# UNIFC-F405.net
KiCad netlist of a schematic drawn in EasyEDA Pro
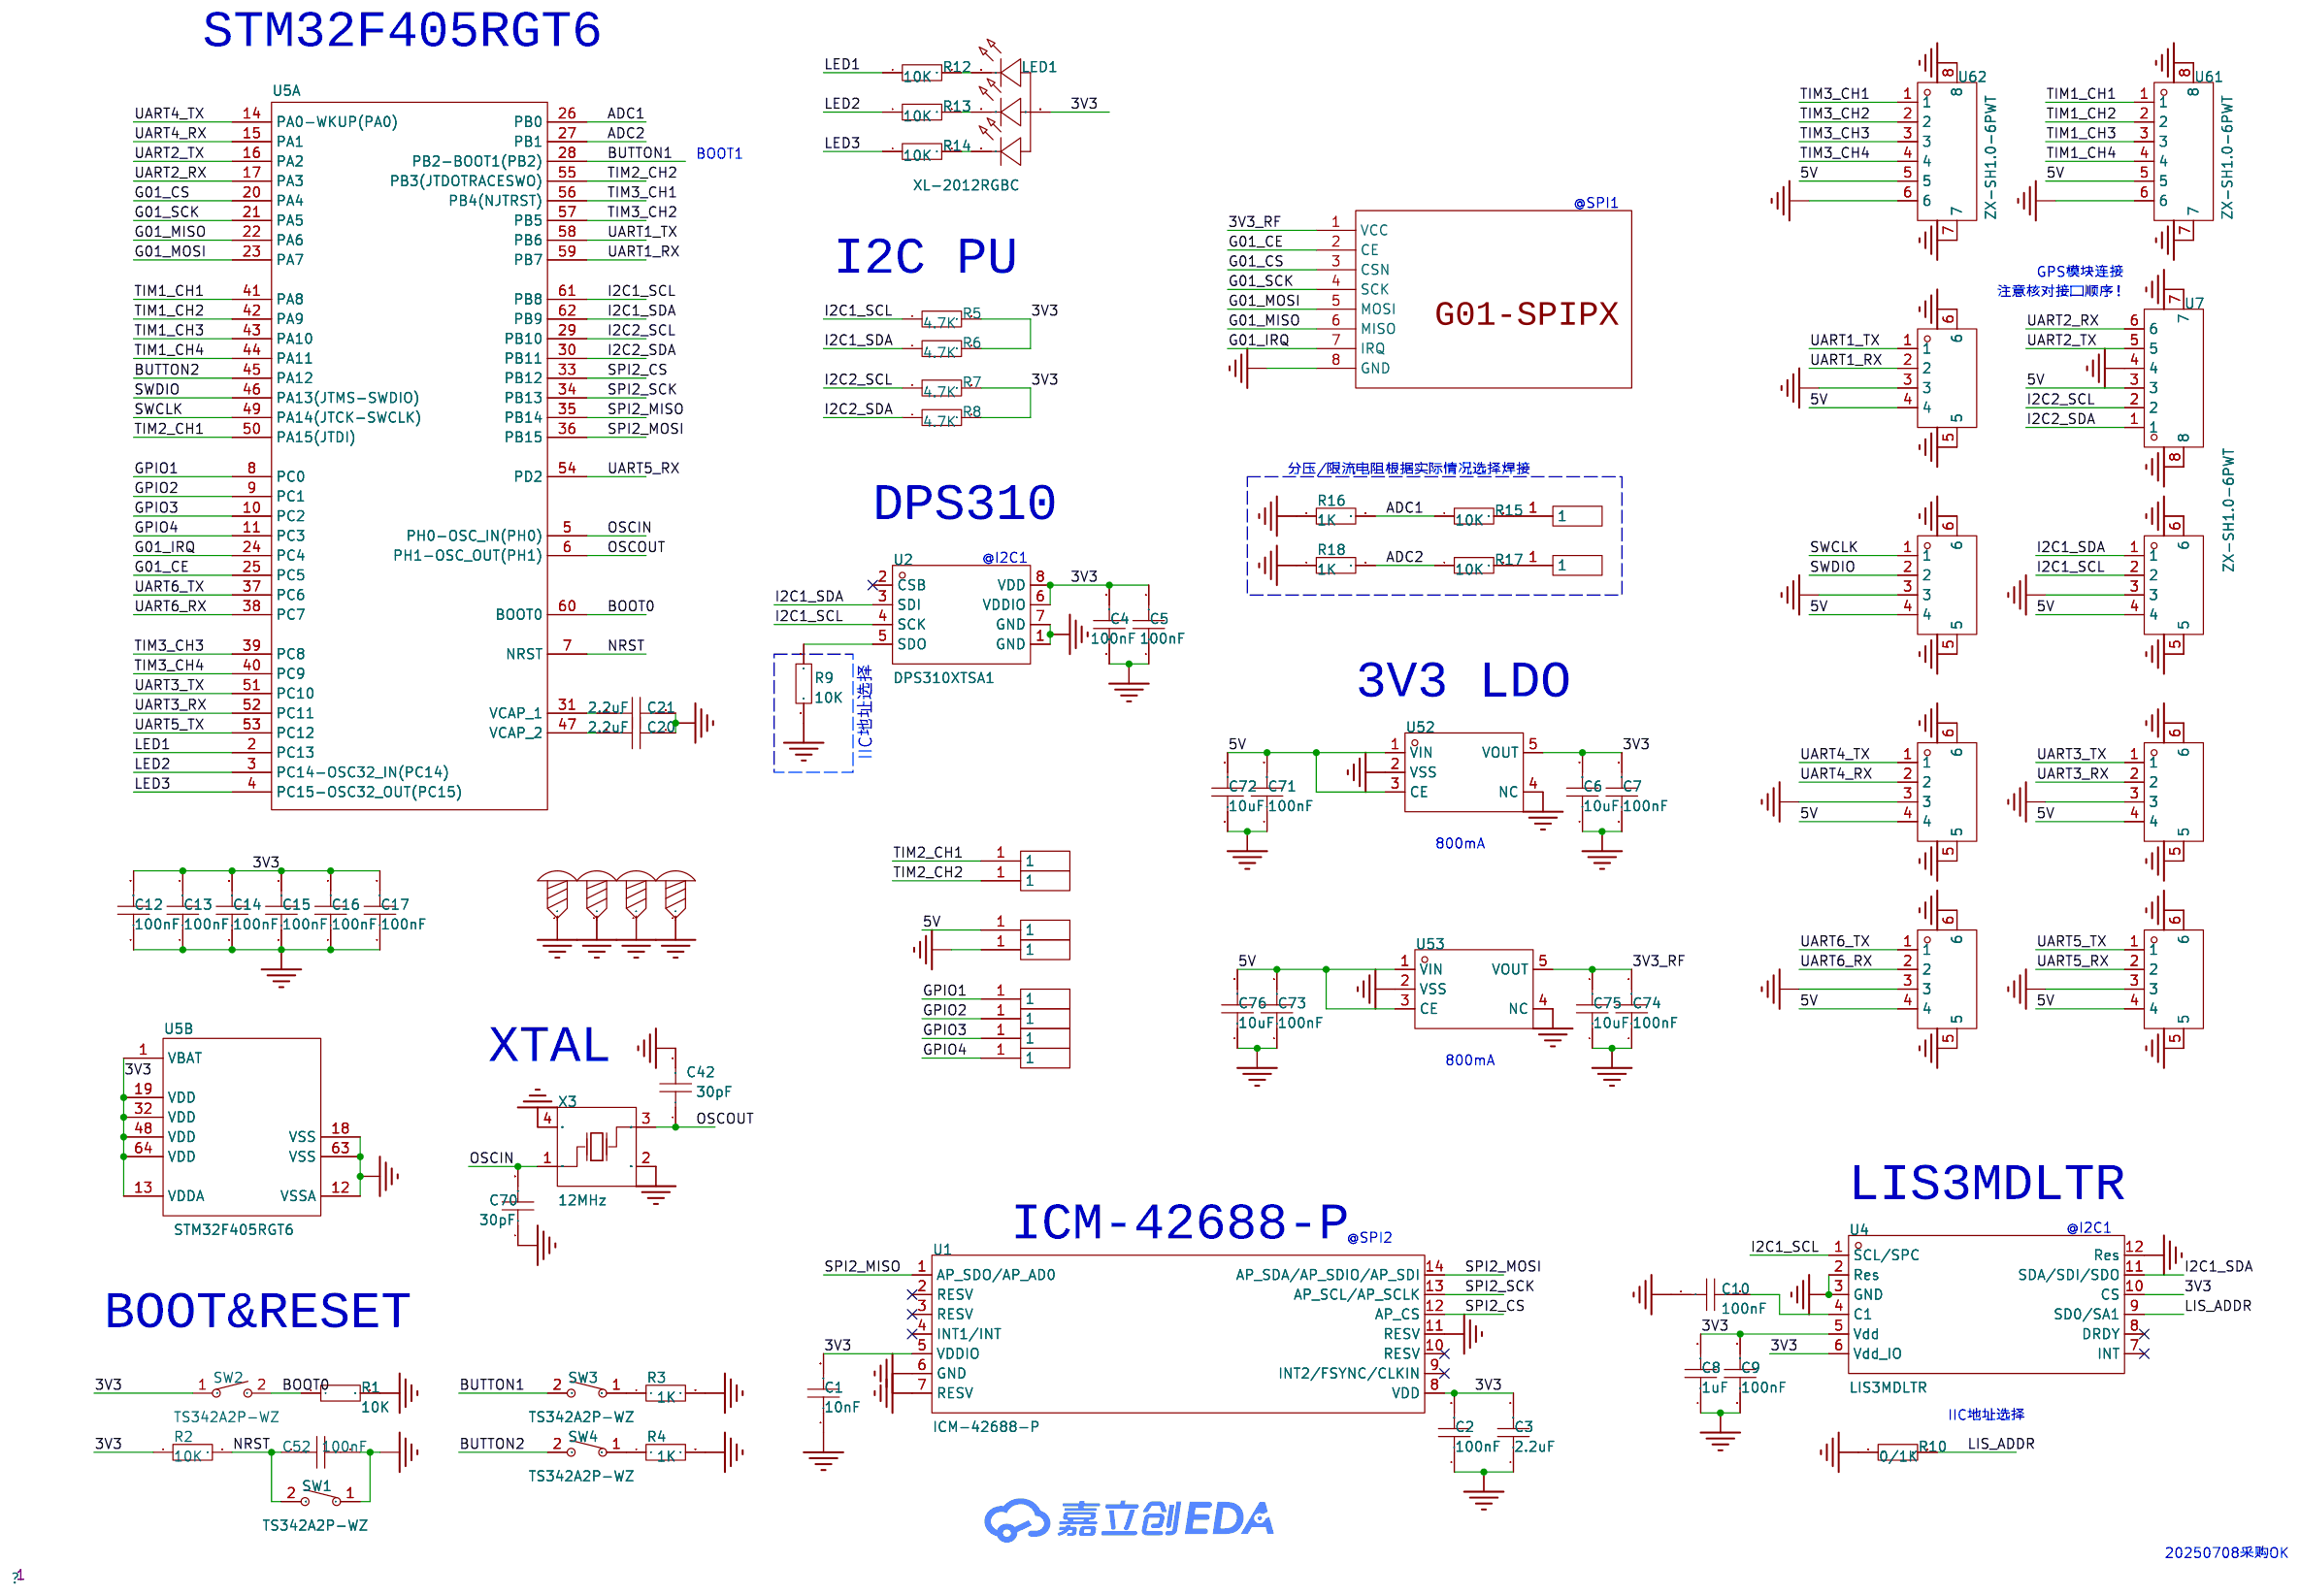
[diagram p0: schematic sheet]

(export (version "E")
  (design (tool "Eeschema 10.0.6"))
  (components
    (comp (ref "C1")
      (value "10nF")
      (footprint "easyedapro:C0603")
      (libsource (lib "easyedapro") (part "CapAcitance"))
    )
    (comp (ref "C2")
      (value "100nF")
      (footprint "easyedapro:C0603")
      (libsource (lib "easyedapro") (part "CapAcitance"))
    )
    (comp (ref "C3")
      (value "2.2uF")
      (footprint "easyedapro:C0603")
      (libsource (lib "easyedapro") (part "CapAcitance"))
    )
    (comp (ref "C4")
      (value "100nF")
      (footprint "easyedapro:C0603")
      (libsource (lib "easyedapro") (part "CapAcitance"))
    )
    (comp (ref "C5")
      (value "100nF")
      (footprint "easyedapro:C0603")
      (libsource (lib "easyedapro") (part "CapAcitance"))
    )
    (comp (ref "C6")
      (value "10uF")
      (footprint "easyedapro:C0603")
      (fields
        (field (name "Manufacturer Part") "CL10A106KP8NNNC")
        (field (name "Manufacturer") "SAMSUNG(三星)")
      )
      (libsource (lib "easyedapro") (part "CapAcitance"))
    )
    (comp (ref "C7")
      (value "100nF")
      (footprint "easyedapro:C0603")
      (fields
        (field (name "Manufacturer Part") "CC0603KRX7R9BB104")
        (field (name "Manufacturer") "YAGEO(国巨)")
      )
      (libsource (lib "easyedapro") (part "CapAcitance"))
    )
    (comp (ref "C8")
      (value "1uF")
      (footprint "easyedapro:C0603")
      (libsource (lib "easyedapro") (part "CapAcitance"))
    )
    (comp (ref "C9")
      (value "100nF")
      (footprint "easyedapro:C0603")
      (libsource (lib "easyedapro") (part "CapAcitance"))
    )
    (comp (ref "C10")
      (value "100nF")
      (footprint "easyedapro:C0603")
      (libsource (lib "easyedapro") (part "CapAcitance"))
    )
    (comp (ref "C12")
      (value "100nF")
      (footprint "easyedapro:C0603")
      (fields
        (field (name "Manufacturer Part") "CC0603KRX7R9BB104")
        (field (name "Manufacturer") "YAGEO(国巨)")
      )
      (libsource (lib "easyedapro") (part "CapAcitance"))
    )
    (comp (ref "C13")
      (value "100nF")
      (footprint "easyedapro:C0603")
      (fields
        (field (name "Manufacturer Part") "CC0603KRX7R9BB104")
        (field (name "Manufacturer") "YAGEO(国巨)")
      )
      (libsource (lib "easyedapro") (part "CapAcitance"))
    )
    (comp (ref "C14")
      (value "100nF")
      (footprint "easyedapro:C0603")
      (fields
        (field (name "Manufacturer Part") "CC0603KRX7R9BB104")
        (field (name "Manufacturer") "YAGEO(国巨)")
      )
      (libsource (lib "easyedapro") (part "CapAcitance"))
    )
    (comp (ref "C15")
      (value "100nF")
      (footprint "easyedapro:C0603")
      (fields
        (field (name "Manufacturer Part") "CC0603KRX7R9BB104")
        (field (name "Manufacturer") "YAGEO(国巨)")
      )
      (libsource (lib "easyedapro") (part "CapAcitance"))
    )
    (comp (ref "C16")
      (value "100nF")
      (footprint "easyedapro:C0603")
      (fields
        (field (name "Manufacturer Part") "CC0603KRX7R9BB104")
        (field (name "Manufacturer") "YAGEO(国巨)")
      )
      (libsource (lib "easyedapro") (part "CapAcitance"))
    )
    (comp (ref "C17")
      (value "100nF")
      (footprint "easyedapro:C0603")
      (fields
        (field (name "Manufacturer Part") "CC0603KRX7R9BB104")
        (field (name "Manufacturer") "YAGEO(国巨)")
      )
      (libsource (lib "easyedapro") (part "CapAcitance"))
    )
    (comp (ref "C20")
      (value "2.2uF")
      (footprint "easyedapro:C0603")
      (fields
        (field (name "Manufacturer Part") "CL10A225KO8NNNC")
        (field (name "Manufacturer") "SAMSUNG(三星)")
      )
      (libsource (lib "easyedapro") (part "CapAcitance"))
    )
    (comp (ref "C21")
      (value "2.2uF")
      (footprint "easyedapro:C0603")
      (fields
        (field (name "Manufacturer Part") "CL10A225KO8NNNC")
        (field (name "Manufacturer") "SAMSUNG(三星)")
      )
      (libsource (lib "easyedapro") (part "CapAcitance"))
    )
    (comp (ref "C42")
      (value "30pF")
      (footprint "easyedapro:C0603")
      (fields (field (name "Manufacturer Part") "0603CG300J500NT") (field (name "Manufacturer") "FH(风华)"))
      (libsource (lib "easyedapro") (part "CapAcitance"))
    )
    (comp (ref "C52")
      (value "100nF")
      (footprint "easyedapro:C0603")
      (fields
        (field (name "Manufacturer Part") "CC0603KRX7R9BB104")
        (field (name "Manufacturer") "YAGEO(国巨)")
      )
      (libsource (lib "easyedapro") (part "CapAcitance"))
    )
    (comp (ref "C70")
      (value "30pF")
      (footprint "easyedapro:C0603")
      (fields (field (name "Manufacturer Part") "0603CG300J500NT") (field (name "Manufacturer") "FH(风华)"))
      (libsource (lib "easyedapro") (part "CapAcitance"))
    )
    (comp (ref "C71")
      (value "100nF")
      (footprint "easyedapro:C0603")
      (fields
        (field (name "Manufacturer Part") "CC0603KRX7R9BB104")
        (field (name "Manufacturer") "YAGEO(国巨)")
      )
      (libsource (lib "easyedapro") (part "CapAcitance"))
    )
    (comp (ref "C72")
      (value "10uF")
      (footprint "easyedapro:C0603")
      (fields
        (field (name "Manufacturer Part") "CC0603KRX7R9BB104")
        (field (name "Manufacturer") "YAGEO(国巨)")
      )
      (libsource (lib "easyedapro") (part "CapAcitance"))
    )
    (comp (ref "C73")
      (value "100nF")
      (footprint "easyedapro:C0603")
      (fields
        (field (name "Manufacturer Part") "CC0603KRX7R9BB104")
        (field (name "Manufacturer") "YAGEO(国巨)")
      )
      (libsource (lib "easyedapro") (part "CapAcitance"))
    )
    (comp (ref "C74")
      (value "100nF")
      (footprint "easyedapro:C0603")
      (fields
        (field (name "Manufacturer Part") "CC0603KRX7R9BB104")
        (field (name "Manufacturer") "YAGEO(国巨)")
      )
      (libsource (lib "easyedapro") (part "CapAcitance"))
    )
    (comp (ref "C75")
      (value "10uF")
      (footprint "easyedapro:C0603")
      (fields
        (field (name "Manufacturer Part") "CL10A106KP8NNNC")
        (field (name "Manufacturer") "SAMSUNG(三星)")
      )
      (libsource (lib "easyedapro") (part "CapAcitance"))
    )
    (comp (ref "C76")
      (value "10uF")
      (footprint "easyedapro:C0603")
      (fields
        (field (name "Manufacturer Part") "CC0603KRX7R9BB104")
        (field (name "Manufacturer") "YAGEO(国巨)")
      )
      (libsource (lib "easyedapro") (part "CapAcitance"))
    )
    (comp (ref "H1")
      (value "~")
      (footprint "easyedapro:飞控微型焊盘")
      (description "20250513 绘制接收机使用")
      (libsource (lib "easyedapro") (part "飞控微型焊盘"))
    )
    (comp (ref "H2")
      (value "~")
      (footprint "easyedapro:飞控微型焊盘")
      (description "20250513 绘制接收机使用")
      (libsource (lib "easyedapro") (part "飞控微型焊盘"))
    )
    (comp (ref "H3")
      (value "~")
      (footprint "easyedapro:飞控微型焊盘")
      (description "20250513 绘制接收机使用")
      (libsource (lib "easyedapro") (part "飞控微型焊盘"))
    )
    (comp (ref "H4")
      (value "~")
      (footprint "easyedapro:飞控微型焊盘")
      (description "20250513 绘制接收机使用")
      (libsource (lib "easyedapro") (part "飞控微型焊盘"))
    )
    (comp (ref "H5")
      (value "~")
      (footprint "easyedapro:飞控微型焊盘")
      (description "20250513 绘制接收机使用")
      (libsource (lib "easyedapro") (part "飞控微型焊盘"))
    )
    (comp (ref "H6")
      (value "~")
      (footprint "easyedapro:飞控微型焊盘")
      (description "20250513 绘制接收机使用")
      (libsource (lib "easyedapro") (part "飞控微型焊盘"))
    )
    (comp (ref "H7")
      (value "~")
      (footprint "easyedapro:飞控微型焊盘")
      (description "20250513 绘制接收机使用")
      (libsource (lib "easyedapro") (part "飞控微型焊盘"))
    )
    (comp (ref "H8")
      (value "~")
      (footprint "easyedapro:飞控微型焊盘")
      (description "20250513 绘制接收机使用")
      (libsource (lib "easyedapro") (part "飞控微型焊盘"))
    )
    (comp (ref "H9")
      (value "~")
      (footprint "easyedapro:飞控微型焊盘")
      (description "20250513 绘制接收机使用")
      (libsource (lib "easyedapro") (part "飞控微型焊盘"))
    )
    (comp (ref "H10")
      (value "~")
      (footprint "easyedapro:飞控微型焊盘")
      (description "20250513 绘制接收机使用")
      (libsource (lib "easyedapro") (part "飞控微型焊盘"))
    )
    (comp (ref "LED1")
      (value "XL-2012RGBC")
      (footprint "easyedapro:LED-SMD_4P-L2.0-W1.3-BR")
      (fields (field (name "Manufacturer") "XINGLIGHT(成兴光)"))
      (libsource (lib "easyedapro") (part "XL-2012RGBC"))
    )
    (comp (ref "R1")
      (value "10K")
      (fields
        (field (name "Manufacturer Part") "0603WAF1002T5E")
        (field (name "Manufacturer") "UNI-ROYAL(厚声)")
      )
      (libsource (lib "easyedapro") (part "电阻"))
    )
    (comp (ref "R2")
      (value "10K")
      (fields
        (field (name "Manufacturer Part") "0603WAF1002T5E")
        (field (name "Manufacturer") "UNI-ROYAL(厚声)")
      )
      (libsource (lib "easyedapro") (part "电阻"))
    )
    (comp (ref "R3") (value "1K") (footprint "easyedapro:R0603") (libsource (lib "easyedapro") (part "电阻")))
    (comp (ref "R4") (value "1K") (footprint "easyedapro:R0603") (libsource (lib "easyedapro") (part "电阻")))
    (comp (ref "R5")
      (value "4.7K")
      (fields
        (field (name "Manufacturer Part") "0603WAF4702T5E")
        (field (name "Manufacturer") "UNI-ROYAL(厚声)")
      )
      (libsource (lib "easyedapro") (part "电阻"))
    )
    (comp (ref "R6")
      (value "4.7K")
      (fields
        (field (name "Manufacturer Part") "0603WAF4702T5E")
        (field (name "Manufacturer") "UNI-ROYAL(厚声)")
      )
      (libsource (lib "easyedapro") (part "电阻"))
    )
    (comp (ref "R7")
      (value "4.7K")
      (fields
        (field (name "Manufacturer Part") "0603WAF4702T5E")
        (field (name "Manufacturer") "UNI-ROYAL(厚声)")
      )
      (libsource (lib "easyedapro") (part "电阻"))
    )
    (comp (ref "R8")
      (value "4.7K")
      (fields
        (field (name "Manufacturer Part") "0603WAF4702T5E")
        (field (name "Manufacturer") "UNI-ROYAL(厚声)")
      )
      (libsource (lib "easyedapro") (part "电阻"))
    )
    (comp (ref "R9") (value "10K") (footprint "easyedapro:R0603") (libsource (lib "easyedapro") (part "电阻")))
    (comp (ref "R10")
      (value "0/1K")
      (footprint "easyedapro:R0603")
      (libsource (lib "easyedapro") (part "电阻"))
    )
    (comp (ref "R12") (value "10K") (footprint "easyedapro:R0603") (libsource (lib "easyedapro") (part "电阻")))
    (comp (ref "R13") (value "10K") (footprint "easyedapro:R0603") (libsource (lib "easyedapro") (part "电阻")))
    (comp (ref "R14") (value "10K") (footprint "easyedapro:R0603") (libsource (lib "easyedapro") (part "电阻")))
    (comp (ref "R15") (value "10K") (footprint "easyedapro:R0603") (libsource (lib "easyedapro") (part "电阻")))
    (comp (ref "R16") (value "1K") (footprint "easyedapro:R0603") (libsource (lib "easyedapro") (part "电阻")))
    (comp (ref "R17") (value "10K") (footprint "easyedapro:R0603") (libsource (lib "easyedapro") (part "电阻")))
    (comp (ref "R18") (value "1K") (footprint "easyedapro:R0603") (libsource (lib "easyedapro") (part "电阻")))
    (comp (ref "SCREW1")
      (value "~")
      (footprint "easyedapro:M3螺丝")
      (libsource (lib "easyedapro") (part "螺丝孔"))
    )
    (comp (ref "SCREW2")
      (value "~")
      (footprint "easyedapro:M3螺丝")
      (libsource (lib "easyedapro") (part "螺丝孔"))
    )
    (comp (ref "SCREW3")
      (value "~")
      (footprint "easyedapro:M3螺丝")
      (libsource (lib "easyedapro") (part "螺丝孔"))
    )
    (comp (ref "SCREW4")
      (value "~")
      (footprint "easyedapro:M3螺丝")
      (libsource (lib "easyedapro") (part "螺丝孔"))
    )
    (comp (ref "SW1")
      (value "TS342A2P-WZ")
      (footprint "easyedapro:SW-SMD_L4.0-W2.9-LS5.0")
      (fields (field (name "Manufacturer") "SHOU HAN(首韩)"))
      (libsource (lib "easyedapro") (part "TS342A2P-WZ"))
    )
    (comp (ref "SW2")
      (value "TS342A2P-WZ")
      (footprint "easyedapro:SW-SMD_L4.0-W2.9-LS5.0")
      (fields (field (name "Manufacturer") "SHOU HAN(首韩)"))
      (libsource (lib "easyedapro") (part "TS342A2P-WZ"))
    )
    (comp (ref "SW3")
      (value "TS342A2P-WZ")
      (footprint "easyedapro:SW-SMD_L4.0-W2.9-LS5.0")
      (fields (field (name "Manufacturer") "SHOU HAN(首韩)"))
      (libsource (lib "easyedapro") (part "TS342A2P-WZ"))
    )
    (comp (ref "SW4")
      (value "TS342A2P-WZ")
      (footprint "easyedapro:SW-SMD_L4.0-W2.9-LS5.0")
      (fields (field (name "Manufacturer") "SHOU HAN(首韩)"))
      (libsource (lib "easyedapro") (part "TS342A2P-WZ"))
    )
    (comp (ref "U1")
      (value "ICM-42688-P")
      (footprint "easyedapro:LGA-14_L3.0-W2.5-P0.50-TL")
      (description "传感器类型:加速度计陀螺仪;")
      (fields (field (name "Manufacturer") "TDK InvenSense(应美盛)"))
      (libsource (lib "easyedapro") (part "ICM-42688-P"))
    )
    (comp (ref "U2")
      (value "DPS310XTSA1")
      (footprint "easyedapro:LGA-8_DPS310XTSA1")
      (description "压力范围:30Kpa~120Kpa;")
      (fields (field (name "Manufacturer") "Infineon(英飞凌)"))
      (libsource (lib "easyedapro") (part "DPS310XTSA1_C3232509"))
    )
    (comp (ref "U4")
      (value "LIS3MDLTR")
      (footprint "easyedapro:LGA-12_L2.0-W2.0-P0.50-BL")
      (description "3轴MEMS磁场传感器，数字输出，I2C/SPI，低功耗模式，高性能")
      (fields (field (name "Manufacturer") "ST(意法半导体)"))
      (libsource (lib "easyedapro") (part "LIS3MDLTR"))
    )
    (comp (ref "U5")
      (value "STM32F405RGT6")
      (footprint "easyedapro:LQFP-64_L10.0-W10.0-P0.50-LS12.0-BL")
      (fields (field (name "Manufacturer") "ST(意法半导体)"))
      (libsource (lib "easyedapro") (part "STM32F405RGT6"))
    )
    (comp (ref "U6") (value "~") (libsource (lib "easyedapro") (part "G01-SPIPX")))
    (comp (ref "U7")
      (value "ZX-SH1.0-6PWT")
      (footprint "easyedapro:CONN-SMD_6P-P1.00_MEGASTAR_ZX-SH1.0-6PWT")
      (description "插针结构:1x6P;间距:1mm;安装方式:卧贴;参考系列:SH;总PIN数:6P;排数:1;每排PIN数:6;行距:-;额定电流:-;触头材质:黄铜;触头镀层:锡;工作温度范围:-;")
      (fields (field (name "Manufacturer") "Megastar(兆星)"))
      (libsource (lib "easyedapro") (part "ZX-SH1.0-6PWT"))
    )
    (comp (ref "U44")
      (value "ZX-SH1.0-4PWT")
      (footprint "easyedapro:CONN-SMD_4P-P1.00_MEGASTAR_ZX-SH1.0-4PWT")
      (description "插针结构:1x4P;间距:1mm;安装方式:卧贴;参考系列:SH;总PIN数:4P;排数:1;每排PIN数:4;行距:-;额定电流:-;触头材质:黄铜;触头镀层:锡;工作温度范围:-;")
      (fields (field (name "Manufacturer") "Megastar(兆星)"))
      (libsource (lib "easyedapro") (part "ZX-SH1.0-4PWT"))
    )
    (comp (ref "U45")
      (value "ZX-SH1.0-4PWT")
      (footprint "easyedapro:CONN-SMD_4P-P1.00_MEGASTAR_ZX-SH1.0-4PWT")
      (description "插针结构:1x4P;间距:1mm;安装方式:卧贴;参考系列:SH;总PIN数:4P;排数:1;每排PIN数:4;行距:-;额定电流:-;触头材质:黄铜;触头镀层:锡;工作温度范围:-;")
      (fields (field (name "Manufacturer") "Megastar(兆星)"))
      (libsource (lib "easyedapro") (part "ZX-SH1.0-4PWT"))
    )
    (comp (ref "U46")
      (value "ZX-SH1.0-4PWT")
      (footprint "easyedapro:CONN-SMD_4P-P1.00_MEGASTAR_ZX-SH1.0-4PWT")
      (description "插针结构:1x4P;间距:1mm;安装方式:卧贴;参考系列:SH;总PIN数:4P;排数:1;每排PIN数:4;行距:-;额定电流:-;触头材质:黄铜;触头镀层:锡;工作温度范围:-;")
      (fields (field (name "Manufacturer") "Megastar(兆星)"))
      (libsource (lib "easyedapro") (part "ZX-SH1.0-4PWT"))
    )
    (comp (ref "U49")
      (value "ZX-SH1.0-4PWT")
      (footprint "easyedapro:CONN-SMD_4P-P1.00_MEGASTAR_ZX-SH1.0-4PWT")
      (description "插针结构:1x4P;间距:1mm;安装方式:卧贴;参考系列:SH;总PIN数:4P;排数:1;每排PIN数:4;行距:-;额定电流:-;触头材质:黄铜;触头镀层:锡;工作温度范围:-;")
      (fields (field (name "Manufacturer") "Megastar(兆星)"))
      (libsource (lib "easyedapro") (part "ZX-SH1.0-4PWT"))
    )
    (comp (ref "U50")
      (value "ZX-SH1.0-4PWT")
      (footprint "easyedapro:CONN-SMD_4P-P1.00_MEGASTAR_ZX-SH1.0-4PWT")
      (description "插针结构:1x4P;间距:1mm;安装方式:卧贴;参考系列:SH;总PIN数:4P;排数:1;每排PIN数:4;行距:-;额定电流:-;触头材质:黄铜;触头镀层:锡;工作温度范围:-;")
      (fields (field (name "Manufacturer") "Megastar(兆星)"))
      (libsource (lib "easyedapro") (part "ZX-SH1.0-4PWT"))
    )
    (comp (ref "U52")
      (value "ME6217C33M5G")
      (footprint "easyedapro:SOT-23-5_L3.0-W1.7-P0.95-LS2.8-BR")
      (description "输出类型:固定;输出极性:正;最大输入电压:7V;输出电压:3.3V;输出电流:800mA;电源纹波抑制比(PSRR):65dB@(1kHz);")
      (fields (field (name "Manufacturer") "MICRONE(南京微盟)"))
      (libsource (lib "easyedapro") (part "ME6217C33M5G"))
    )
    (comp (ref "U53")
      (value "ME6217C33M5G")
      (footprint "easyedapro:SOT-23-5_L3.0-W1.7-P0.95-LS2.8-BR")
      (description "输出类型:固定;输出极性:正;最大输入电压:7V;输出电压:3.3V;输出电流:800mA;电源纹波抑制比(PSRR):65dB@(1kHz);")
      (fields (field (name "Manufacturer") "MICRONE(南京微盟)"))
      (libsource (lib "easyedapro") (part "ME6217C33M5G"))
    )
    (comp (ref "U59")
      (value "ZX-SH1.0-4PWT")
      (footprint "easyedapro:CONN-SMD_4P-P1.00_MEGASTAR_ZX-SH1.0-4PWT")
      (description "插针结构:1x4P;间距:1mm;安装方式:卧贴;参考系列:SH;总PIN数:4P;排数:1;每排PIN数:4;行距:-;额定电流:-;触头材质:黄铜;触头镀层:锡;工作温度范围:-;")
      (fields (field (name "Manufacturer") "Megastar(兆星)"))
      (libsource (lib "easyedapro") (part "ZX-SH1.0-4PWT"))
    )
    (comp (ref "U60")
      (value "ZX-SH1.0-4PWT")
      (footprint "easyedapro:CONN-SMD_4P-P1.00_MEGASTAR_ZX-SH1.0-4PWT")
      (description "插针结构:1x4P;间距:1mm;安装方式:卧贴;参考系列:SH;总PIN数:4P;排数:1;每排PIN数:4;行距:-;额定电流:-;触头材质:黄铜;触头镀层:锡;工作温度范围:-;")
      (fields (field (name "Manufacturer") "Megastar(兆星)"))
      (libsource (lib "easyedapro") (part "ZX-SH1.0-4PWT"))
    )
    (comp (ref "U61")
      (value "ZX-SH1.0-6PWT")
      (footprint "easyedapro:CONN-SMD_6P-P1.00_MEGASTAR_ZX-SH1.0-6PWT")
      (description "插针结构:1x6P;间距:1mm;安装方式:卧贴;参考系列:SH;总PIN数:6P;排数:1;每排PIN数:6;行距:-;额定电流:-;触头材质:黄铜;触头镀层:锡;工作温度范围:-;")
      (fields (field (name "Manufacturer") "Megastar(兆星)"))
      (libsource (lib "easyedapro") (part "ZX-SH1.0-6PWT"))
    )
    (comp (ref "U62")
      (value "ZX-SH1.0-6PWT")
      (footprint "easyedapro:CONN-SMD_6P-P1.00_MEGASTAR_ZX-SH1.0-6PWT")
      (description "插针结构:1x6P;间距:1mm;安装方式:卧贴;参考系列:SH;总PIN数:6P;排数:1;每排PIN数:6;行距:-;额定电流:-;触头材质:黄铜;触头镀层:锡;工作温度范围:-;")
      (fields (field (name "Manufacturer") "Megastar(兆星)"))
      (libsource (lib "easyedapro") (part "ZX-SH1.0-6PWT"))
    )
    (comp (ref "X3")
      (value "12MHz")
      (footprint "easyedapro:CRYSTAL-SMD_4P-L3.2-W2.5-BL")
      (description "晶振类型:贴片晶振;频率:12MHz;常温频差:±10ppm;外接负载电容:20pF;频率稳定度(全温):±20ppm;")
      (fields (field (name "Manufacturer Part") "X322512MSB4SI") (field (name "Manufacturer") "YXC(扬兴晶振)"))
      (libsource (lib "easyedapro") (part "X322512MSB4SI"))
    )
  )
  (nets
    (net (code "1") (name "/3V3") (class "Default")
      (node (ref "C1") (pin "2") (pinfunction "2_2") (pintype "input"))
      (node (ref "C12") (pin "2") (pinfunction "2_2") (pintype "input"))
      (node (ref "C13") (pin "2") (pinfunction "2_2") (pintype "input"))
      (node (ref "C14") (pin "2") (pinfunction "2_2") (pintype "input"))
      (node (ref "C15") (pin "2") (pinfunction "2_2") (pintype "input"))
      (node (ref "C16") (pin "2") (pinfunction "2_2") (pintype "input"))
      (node (ref "C17") (pin "2") (pinfunction "2_2") (pintype "input"))
      (node (ref "C2") (pin "2") (pinfunction "2_2") (pintype "input"))
      (node (ref "C3") (pin "2") (pinfunction "2_2") (pintype "input"))
      (node (ref "C4") (pin "2") (pinfunction "2_2") (pintype "input"))
      (node (ref "C5") (pin "2") (pinfunction "2_2") (pintype "input"))
      (node (ref "C6") (pin "2") (pinfunction "2_2") (pintype "input"))
      (node (ref "C7") (pin "2") (pinfunction "2_2") (pintype "input"))
      (node (ref "C8") (pin "2") (pinfunction "2_2") (pintype "input"))
      (node (ref "C9") (pin "2") (pinfunction "2_2") (pintype "input"))
      (node (ref "LED1") (pin "3") (pinfunction "3_3") (pintype "unspecified"))
      (node (ref "R2") (pin "1") (pinfunction "1_1") (pintype "input"))
      (node (ref "R5") (pin "2") (pinfunction "2_2") (pintype "input"))
      (node (ref "R6") (pin "2") (pinfunction "2_2") (pintype "input"))
      (node (ref "R7") (pin "2") (pinfunction "2_2") (pintype "input"))
      (node (ref "R8") (pin "2") (pinfunction "2_2") (pintype "input"))
      (node (ref "SW2") (pin "1") (pinfunction "1_1") (pintype "unspecified"))
      (node (ref "U1") (pin "5") (pinfunction "VDDIO_5") (pintype "unspecified"))
      (node (ref "U1") (pin "8") (pinfunction "VDD_8") (pintype "unspecified"))
      (node (ref "U2") (pin "6") (pinfunction "VDDIO_6") (pintype "unspecified"))
      (node (ref "U2") (pin "8") (pinfunction "VDD_8") (pintype "unspecified"))
      (node (ref "U4") (pin "10") (pinfunction "CS_10") (pintype "unspecified"))
      (node (ref "U4") (pin "5") (pinfunction "Vdd_5") (pintype "unspecified"))
      (node (ref "U4") (pin "6") (pinfunction "Vdd_IO_6") (pintype "unspecified"))
      (node (ref "U5") (pin "1") (pinfunction "VBAT_1") (pintype "unspecified"))
      (node (ref "U5") (pin "13") (pinfunction "VDDA_13") (pintype "unspecified"))
      (node (ref "U5") (pin "19") (pinfunction "VDD_19") (pintype "unspecified"))
      (node (ref "U5") (pin "32") (pinfunction "VDD_32") (pintype "unspecified"))
      (node (ref "U5") (pin "48") (pinfunction "VDD_48") (pintype "unspecified"))
      (node (ref "U5") (pin "64") (pinfunction "VDD_64") (pintype "unspecified"))
      (node (ref "U52") (pin "5") (pinfunction "VOUT_5") (pintype "input"))
    )
    (net (code "2") (name "/3V3_RF") (class "Default")
      (node (ref "C74") (pin "2") (pinfunction "2_2") (pintype "input"))
      (node (ref "C75") (pin "2") (pinfunction "2_2") (pintype "input"))
      (node (ref "U53") (pin "5") (pinfunction "VOUT_5") (pintype "input"))
      (node (ref "U6") (pin "1") (pinfunction "VCC_1") (pintype "input"))
    )
    (net (code "3") (name "/5V") (class "Default")
      (node (ref "C71") (pin "2") (pinfunction "2_2") (pintype "input"))
      (node (ref "C72") (pin "2") (pinfunction "2_2") (pintype "input"))
      (node (ref "C73") (pin "2") (pinfunction "2_2") (pintype "input"))
      (node (ref "C76") (pin "2") (pinfunction "2_2") (pintype "input"))
      (node (ref "H9") (pin "1") (pinfunction "1_1") (pintype "input"))
      (node (ref "U44") (pin "4") (pinfunction "4_4") (pintype "unspecified"))
      (node (ref "U45") (pin "4") (pinfunction "4_4") (pintype "unspecified"))
      (node (ref "U46") (pin "4") (pinfunction "4_4") (pintype "unspecified"))
      (node (ref "U49") (pin "4") (pinfunction "4_4") (pintype "unspecified"))
      (node (ref "U50") (pin "4") (pinfunction "4_4") (pintype "unspecified"))
      (node (ref "U52") (pin "1") (pinfunction "VIN_1") (pintype "input"))
      (node (ref "U52") (pin "3") (pinfunction "CE_3") (pintype "input"))
      (node (ref "U53") (pin "1") (pinfunction "VIN_1") (pintype "input"))
      (node (ref "U53") (pin "3") (pinfunction "CE_3") (pintype "input"))
      (node (ref "U59") (pin "4") (pinfunction "4_4") (pintype "unspecified"))
      (node (ref "U60") (pin "4") (pinfunction "4_4") (pintype "unspecified"))
      (node (ref "U61") (pin "5") (pinfunction "5_5") (pintype "unspecified"))
      (node (ref "U62") (pin "5") (pinfunction "5_5") (pintype "unspecified"))
      (node (ref "U7") (pin "3") (pinfunction "3_3") (pintype "unspecified"))
    )
    (net (code "4") (name "/ADC1") (class "Default")
      (node (ref "R15") (pin "1") (pinfunction "1_1") (pintype "input"))
      (node (ref "R16") (pin "2") (pinfunction "2_2") (pintype "input"))
      (node (ref "U5") (pin "26") (pinfunction "PB0_26") (pintype "bidirectional"))
    )
    (net (code "5") (name "/ADC2") (class "Default")
      (node (ref "R17") (pin "1") (pinfunction "1_1") (pintype "input"))
      (node (ref "R18") (pin "2") (pinfunction "2_2") (pintype "input"))
      (node (ref "U5") (pin "27") (pinfunction "PB1_27") (pintype "bidirectional"))
    )
    (net (code "6") (name "/BOOT0") (class "Default")
      (node (ref "R1") (pin "1") (pinfunction "1_1") (pintype "input"))
      (node (ref "SW2") (pin "2") (pinfunction "2_2") (pintype "unspecified"))
      (node (ref "U5") (pin "60") (pinfunction "BOOT0_60") (pintype "unspecified"))
    )
    (net (code "7") (name "/BUTTON1") (class "Default")
      (node (ref "SW3") (pin "2") (pinfunction "2_2") (pintype "unspecified"))
      (node (ref "U5") (pin "28") (pinfunction "PB2-BOOT1(PB2)_28") (pintype "bidirectional"))
    )
    (net (code "8") (name "/BUTTON2") (class "Default")
      (node (ref "SW4") (pin "2") (pinfunction "2_2") (pintype "unspecified"))
      (node (ref "U5") (pin "45") (pinfunction "PA12_45") (pintype "bidirectional"))
    )
    (net (code "9") (name "/G01_CE") (class "Default")
      (node (ref "U5") (pin "25") (pinfunction "PC5_25") (pintype "bidirectional"))
      (node (ref "U6") (pin "2") (pinfunction "CE_2") (pintype "input"))
    )
    (net (code "10") (name "/G01_CS") (class "Default")
      (node (ref "U5") (pin "20") (pinfunction "PA4_20") (pintype "bidirectional"))
      (node (ref "U6") (pin "3") (pinfunction "CSN_3") (pintype "input"))
    )
    (net (code "11") (name "/G01_IRQ") (class "Default")
      (node (ref "U5") (pin "24") (pinfunction "PC4_24") (pintype "bidirectional"))
      (node (ref "U6") (pin "7") (pinfunction "IRQ_7") (pintype "input"))
    )
    (net (code "12") (name "/G01_MISO") (class "Default")
      (node (ref "U5") (pin "22") (pinfunction "PA6_22") (pintype "bidirectional"))
      (node (ref "U6") (pin "6") (pinfunction "MISO_6") (pintype "input"))
    )
    (net (code "13") (name "/G01_MOSI") (class "Default")
      (node (ref "U5") (pin "23") (pinfunction "PA7_23") (pintype "bidirectional"))
      (node (ref "U6") (pin "5") (pinfunction "MOSI_5") (pintype "input"))
    )
    (net (code "14") (name "/G01_SCK") (class "Default")
      (node (ref "U5") (pin "21") (pinfunction "PA5_21") (pintype "bidirectional"))
      (node (ref "U6") (pin "4") (pinfunction "SCK_4") (pintype "input"))
    )
    (net (code "15") (name "/GPIO1") (class "Default")
      (node (ref "H3") (pin "1") (pinfunction "1_1") (pintype "input"))
      (node (ref "U5") (pin "8") (pinfunction "PC0_8") (pintype "bidirectional"))
    )
    (net (code "16") (name "/GPIO2") (class "Default")
      (node (ref "H4") (pin "1") (pinfunction "1_1") (pintype "input"))
      (node (ref "U5") (pin "9") (pinfunction "PC1_9") (pintype "bidirectional"))
    )
    (net (code "17") (name "/GPIO3") (class "Default")
      (node (ref "H5") (pin "1") (pinfunction "1_1") (pintype "input"))
      (node (ref "U5") (pin "10") (pinfunction "PC2_10") (pintype "bidirectional"))
    )
    (net (code "18") (name "/GPIO4") (class "Default")
      (node (ref "H6") (pin "1") (pinfunction "1_1") (pintype "input"))
      (node (ref "U5") (pin "11") (pinfunction "PC3_11") (pintype "bidirectional"))
    )
    (net (code "19") (name "/I2C1_SCL") (class "Default")
      (node (ref "R5") (pin "1") (pinfunction "1_1") (pintype "input"))
      (node (ref "U2") (pin "4") (pinfunction "SCK_4") (pintype "unspecified"))
      (node (ref "U4") (pin "1") (pinfunction "SCL/SPC_1") (pintype "unspecified"))
      (node (ref "U45") (pin "2") (pinfunction "2_2") (pintype "unspecified"))
      (node (ref "U5") (pin "61") (pinfunction "PB8_61") (pintype "bidirectional"))
    )
    (net (code "20") (name "/I2C1_SDA") (class "Default")
      (node (ref "R6") (pin "1") (pinfunction "1_1") (pintype "input"))
      (node (ref "U2") (pin "3") (pinfunction "SDI_3") (pintype "unspecified"))
      (node (ref "U4") (pin "11") (pinfunction "SDA/SDI/SDO_11") (pintype "unspecified"))
      (node (ref "U45") (pin "1") (pinfunction "1_1") (pintype "unspecified"))
      (node (ref "U5") (pin "62") (pinfunction "PB9_62") (pintype "bidirectional"))
    )
    (net (code "21") (name "/I2C2_SCL") (class "Default")
      (node (ref "R7") (pin "1") (pinfunction "1_1") (pintype "input"))
      (node (ref "U5") (pin "29") (pinfunction "PB10_29") (pintype "bidirectional"))
      (node (ref "U7") (pin "2") (pinfunction "2_2") (pintype "unspecified"))
    )
    (net (code "22") (name "/I2C2_SDA") (class "Default")
      (node (ref "R8") (pin "1") (pinfunction "1_1") (pintype "input"))
      (node (ref "U5") (pin "30") (pinfunction "PB11_30") (pintype "bidirectional"))
      (node (ref "U7") (pin "1") (pinfunction "1_1") (pintype "unspecified"))
    )
    (net (code "23") (name "/LED1") (class "Default")
      (node (ref "R12") (pin "1") (pinfunction "1_1") (pintype "input"))
      (node (ref "U5") (pin "2") (pinfunction "PC13_2") (pintype "bidirectional"))
    )
    (net (code "24") (name "/LED2") (class "Default")
      (node (ref "R13") (pin "1") (pinfunction "1_1") (pintype "input"))
      (node (ref "U5") (pin "3") (pinfunction "PC14-OSC32_IN(PC14)_3") (pintype "bidirectional"))
    )
    (net (code "25") (name "/LED3") (class "Default")
      (node (ref "R14") (pin "1") (pinfunction "1_1") (pintype "input"))
      (node (ref "U5") (pin "4") (pinfunction "PC15-OSC32_OUT(PC15)_4") (pintype "bidirectional"))
    )
    (net (code "26") (name "/LIS_ADDR") (class "Default")
      (node (ref "R10") (pin "2") (pinfunction "2_2") (pintype "input"))
      (node (ref "U4") (pin "9") (pinfunction "SD0/SA1_9") (pintype "unspecified"))
    )
    (net (code "27") (name "/NRST") (class "Default")
      (node (ref "C52") (pin "1") (pinfunction "1_1") (pintype "input"))
      (node (ref "R2") (pin "2") (pinfunction "2_2") (pintype "input"))
      (node (ref "SW1") (pin "2") (pinfunction "2_2") (pintype "unspecified"))
      (node (ref "U5") (pin "7") (pinfunction "NRST_7") (pintype "bidirectional"))
    )
    (net (code "28") (name "/OSCIN") (class "Default")
      (node (ref "C70") (pin "2") (pinfunction "2_2") (pintype "input"))
      (node (ref "U5") (pin "5") (pinfunction "PH0-OSC_IN(PH0)_5") (pintype "bidirectional"))
      (node (ref "X3") (pin "1") (pinfunction "OSC1_1") (pintype "unspecified"))
    )
    (net (code "29") (name "/OSCOUT") (class "Default")
      (node (ref "C42") (pin "1") (pinfunction "1_1") (pintype "input"))
      (node (ref "U5") (pin "6") (pinfunction "PH1-OSC_OUT(PH1)_6") (pintype "bidirectional"))
      (node (ref "X3") (pin "3") (pinfunction "OSC2_3") (pintype "unspecified"))
    )
    (net (code "30") (name "/SPI2_CS") (class "Default")
      (node (ref "U1") (pin "12") (pinfunction "AP_CS_12") (pintype "unspecified"))
      (node (ref "U5") (pin "33") (pinfunction "PB12_33") (pintype "bidirectional"))
    )
    (net (code "31") (name "/SPI2_MISO") (class "Default")
      (node (ref "U1") (pin "1") (pinfunction "AP_SDO/AP_AD0_1") (pintype "unspecified"))
      (node (ref "U5") (pin "35") (pinfunction "PB14_35") (pintype "bidirectional"))
    )
    (net (code "32") (name "/SPI2_MOSI") (class "Default")
      (node (ref "U1") (pin "14") (pinfunction "AP_SDA/AP_SDIO/AP_SDI_14") (pintype "unspecified"))
      (node (ref "U5") (pin "36") (pinfunction "PB15_36") (pintype "bidirectional"))
    )
    (net (code "33") (name "/SPI2_SCK") (class "Default")
      (node (ref "U1") (pin "13") (pinfunction "AP_SCL/AP_SCLK_13") (pintype "unspecified"))
      (node (ref "U5") (pin "34") (pinfunction "PB13_34") (pintype "bidirectional"))
    )
    (net (code "34") (name "/SWCLK") (class "Default")
      (node (ref "U44") (pin "1") (pinfunction "1_1") (pintype "unspecified"))
      (node (ref "U5") (pin "49") (pinfunction "PA14(JTCK-SWCLK)_49") (pintype "bidirectional"))
    )
    (net (code "35") (name "/SWDIO") (class "Default")
      (node (ref "U44") (pin "2") (pinfunction "2_2") (pintype "unspecified"))
      (node (ref "U5") (pin "46") (pinfunction "PA13(JTMS-SWDIO)_46") (pintype "bidirectional"))
    )
    (net (code "36") (name "/TIM1_CH1") (class "Default")
      (node (ref "U5") (pin "41") (pinfunction "PA8_41") (pintype "bidirectional"))
      (node (ref "U61") (pin "1") (pinfunction "1_1") (pintype "unspecified"))
    )
    (net (code "37") (name "/TIM1_CH2") (class "Default")
      (node (ref "U5") (pin "42") (pinfunction "PA9_42") (pintype "bidirectional"))
      (node (ref "U61") (pin "2") (pinfunction "2_2") (pintype "unspecified"))
    )
    (net (code "38") (name "/TIM1_CH3") (class "Default")
      (node (ref "U5") (pin "43") (pinfunction "PA10_43") (pintype "bidirectional"))
      (node (ref "U61") (pin "3") (pinfunction "3_3") (pintype "unspecified"))
    )
    (net (code "39") (name "/TIM1_CH4") (class "Default")
      (node (ref "U5") (pin "44") (pinfunction "PA11_44") (pintype "bidirectional"))
      (node (ref "U61") (pin "4") (pinfunction "4_4") (pintype "unspecified"))
    )
    (net (code "40") (name "/TIM2_CH1") (class "Default")
      (node (ref "H7") (pin "1") (pinfunction "1_1") (pintype "input"))
      (node (ref "U5") (pin "50") (pinfunction "PA15(JTDI)_50") (pintype "bidirectional"))
    )
    (net (code "41") (name "/TIM2_CH2") (class "Default")
      (node (ref "H8") (pin "1") (pinfunction "1_1") (pintype "input"))
      (node (ref "U5") (pin "55") (pinfunction "PB3(JTDOTRACESWO)_55") (pintype "bidirectional"))
    )
    (net (code "42") (name "/TIM3_CH1") (class "Default")
      (node (ref "U5") (pin "56") (pinfunction "PB4(NJTRST)_56") (pintype "bidirectional"))
      (node (ref "U62") (pin "1") (pinfunction "1_1") (pintype "unspecified"))
    )
    (net (code "43") (name "/TIM3_CH2") (class "Default")
      (node (ref "U5") (pin "57") (pinfunction "PB5_57") (pintype "bidirectional"))
      (node (ref "U62") (pin "2") (pinfunction "2_2") (pintype "unspecified"))
    )
    (net (code "44") (name "/TIM3_CH3") (class "Default")
      (node (ref "U5") (pin "39") (pinfunction "PC8_39") (pintype "bidirectional"))
      (node (ref "U62") (pin "3") (pinfunction "3_3") (pintype "unspecified"))
    )
    (net (code "45") (name "/TIM3_CH4") (class "Default")
      (node (ref "U5") (pin "40") (pinfunction "PC9_40") (pintype "bidirectional"))
      (node (ref "U62") (pin "4") (pinfunction "4_4") (pintype "unspecified"))
    )
    (net (code "46") (name "/UART1_RX") (class "Default")
      (node (ref "U49") (pin "2") (pinfunction "2_2") (pintype "unspecified"))
      (node (ref "U5") (pin "59") (pinfunction "PB7_59") (pintype "bidirectional"))
    )
    (net (code "47") (name "/UART1_TX") (class "Default")
      (node (ref "U49") (pin "1") (pinfunction "1_1") (pintype "unspecified"))
      (node (ref "U5") (pin "58") (pinfunction "PB6_58") (pintype "bidirectional"))
    )
    (net (code "48") (name "/UART2_RX") (class "Default")
      (node (ref "U5") (pin "17") (pinfunction "PA3_17") (pintype "bidirectional"))
      (node (ref "U7") (pin "6") (pinfunction "6_6") (pintype "unspecified"))
    )
    (net (code "49") (name "/UART2_TX") (class "Default")
      (node (ref "U5") (pin "16") (pinfunction "PA2_16") (pintype "bidirectional"))
      (node (ref "U7") (pin "5") (pinfunction "5_5") (pintype "unspecified"))
    )
    (net (code "50") (name "/UART3_RX") (class "Default")
      (node (ref "U5") (pin "52") (pinfunction "PC11_52") (pintype "bidirectional"))
      (node (ref "U50") (pin "2") (pinfunction "2_2") (pintype "unspecified"))
    )
    (net (code "51") (name "/UART3_TX") (class "Default")
      (node (ref "U5") (pin "51") (pinfunction "PC10_51") (pintype "bidirectional"))
      (node (ref "U50") (pin "1") (pinfunction "1_1") (pintype "unspecified"))
    )
    (net (code "52") (name "/UART4_RX") (class "Default")
      (node (ref "U46") (pin "2") (pinfunction "2_2") (pintype "unspecified"))
      (node (ref "U5") (pin "15") (pinfunction "PA1_15") (pintype "bidirectional"))
    )
    (net (code "53") (name "/UART4_TX") (class "Default")
      (node (ref "U46") (pin "1") (pinfunction "1_1") (pintype "unspecified"))
      (node (ref "U5") (pin "14") (pinfunction "PA0-WKUP(PA0)_14") (pintype "bidirectional"))
    )
    (net (code "54") (name "/UART5_RX") (class "Default")
      (node (ref "U5") (pin "54") (pinfunction "PD2_54") (pintype "bidirectional"))
      (node (ref "U60") (pin "2") (pinfunction "2_2") (pintype "unspecified"))
    )
    (net (code "55") (name "/UART5_TX") (class "Default")
      (node (ref "U5") (pin "53") (pinfunction "PC12_53") (pintype "bidirectional"))
      (node (ref "U60") (pin "1") (pinfunction "1_1") (pintype "unspecified"))
    )
    (net (code "56") (name "/UART6_RX") (class "Default")
      (node (ref "U5") (pin "38") (pinfunction "PC7_38") (pintype "bidirectional"))
      (node (ref "U59") (pin "2") (pinfunction "2_2") (pintype "unspecified"))
    )
    (net (code "57") (name "/UART6_TX") (class "Default")
      (node (ref "U5") (pin "37") (pinfunction "PC6_37") (pintype "bidirectional"))
      (node (ref "U59") (pin "1") (pinfunction "1_1") (pintype "unspecified"))
    )
    (net (code "58") (name "GND") (class "Default")
      (node (ref "C1") (pin "1") (pinfunction "1_1") (pintype "input"))
      (node (ref "C10") (pin "1") (pinfunction "1_1") (pintype "input"))
      (node (ref "C12") (pin "1") (pinfunction "1_1") (pintype "input"))
      (node (ref "C13") (pin "1") (pinfunction "1_1") (pintype "input"))
      (node (ref "C14") (pin "1") (pinfunction "1_1") (pintype "input"))
      (node (ref "C15") (pin "1") (pinfunction "1_1") (pintype "input"))
      (node (ref "C16") (pin "1") (pinfunction "1_1") (pintype "input"))
      (node (ref "C17") (pin "1") (pinfunction "1_1") (pintype "input"))
      (node (ref "C2") (pin "1") (pinfunction "1_1") (pintype "input"))
      (node (ref "C20") (pin "1") (pinfunction "1_1") (pintype "input"))
      (node (ref "C21") (pin "1") (pinfunction "1_1") (pintype "input"))
      (node (ref "C3") (pin "1") (pinfunction "1_1") (pintype "input"))
      (node (ref "C4") (pin "1") (pinfunction "1_1") (pintype "input"))
      (node (ref "C42") (pin "2") (pinfunction "2_2") (pintype "input"))
      (node (ref "C5") (pin "1") (pinfunction "1_1") (pintype "input"))
      (node (ref "C52") (pin "2") (pinfunction "2_2") (pintype "input"))
      (node (ref "C6") (pin "1") (pinfunction "1_1") (pintype "input"))
      (node (ref "C7") (pin "1") (pinfunction "1_1") (pintype "input"))
      (node (ref "C70") (pin "1") (pinfunction "1_1") (pintype "input"))
      (node (ref "C71") (pin "1") (pinfunction "1_1") (pintype "input"))
      (node (ref "C72") (pin "1") (pinfunction "1_1") (pintype "input"))
      (node (ref "C73") (pin "1") (pinfunction "1_1") (pintype "input"))
      (node (ref "C74") (pin "1") (pinfunction "1_1") (pintype "input"))
      (node (ref "C75") (pin "1") (pinfunction "1_1") (pintype "input"))
      (node (ref "C76") (pin "1") (pinfunction "1_1") (pintype "input"))
      (node (ref "C8") (pin "1") (pinfunction "1_1") (pintype "input"))
      (node (ref "C9") (pin "1") (pinfunction "1_1") (pintype "input"))
      (node (ref "H10") (pin "1") (pinfunction "1_1") (pintype "input"))
      (node (ref "R1") (pin "2") (pinfunction "2_2") (pintype "input"))
      (node (ref "R10") (pin "1") (pinfunction "1_1") (pintype "input"))
      (node (ref "R16") (pin "1") (pinfunction "1_1") (pintype "input"))
      (node (ref "R18") (pin "1") (pinfunction "1_1") (pintype "input"))
      (node (ref "R3") (pin "2") (pinfunction "2_2") (pintype "input"))
      (node (ref "R4") (pin "2") (pinfunction "2_2") (pintype "input"))
      (node (ref "R9") (pin "1") (pinfunction "1_1") (pintype "input"))
      (node (ref "SCREW1") (pin "1") (pinfunction "1_1") (pintype "input"))
      (node (ref "SCREW2") (pin "1") (pinfunction "1_1") (pintype "input"))
      (node (ref "SCREW3") (pin "1") (pinfunction "1_1") (pintype "input"))
      (node (ref "SCREW4") (pin "1") (pinfunction "1_1") (pintype "input"))
      (node (ref "SW1") (pin "1") (pinfunction "1_1") (pintype "unspecified"))
      (node (ref "U1") (pin "11") (pinfunction "RESV_11") (pintype "unspecified"))
      (node (ref "U1") (pin "6") (pinfunction "GND_6") (pintype "unspecified"))
      (node (ref "U1") (pin "7") (pinfunction "RESV_7") (pintype "unspecified"))
      (node (ref "U2") (pin "1") (pinfunction "GND_1") (pintype "unspecified"))
      (node (ref "U2") (pin "7") (pinfunction "GND_7") (pintype "unspecified"))
      (node (ref "U4") (pin "12") (pinfunction "Res_12") (pintype "unspecified"))
      (node (ref "U4") (pin "2") (pinfunction "Res_2") (pintype "unspecified"))
      (node (ref "U4") (pin "3") (pinfunction "GND_3") (pintype "unspecified"))
      (node (ref "U44") (pin "3") (pinfunction "3_3") (pintype "unspecified"))
      (node (ref "U44") (pin "5") (pinfunction "5_5") (pintype "unspecified"))
      (node (ref "U44") (pin "6") (pinfunction "6_6") (pintype "unspecified"))
      (node (ref "U45") (pin "3") (pinfunction "3_3") (pintype "unspecified"))
      (node (ref "U45") (pin "5") (pinfunction "5_5") (pintype "unspecified"))
      (node (ref "U45") (pin "6") (pinfunction "6_6") (pintype "unspecified"))
      (node (ref "U46") (pin "3") (pinfunction "3_3") (pintype "unspecified"))
      (node (ref "U46") (pin "5") (pinfunction "5_5") (pintype "unspecified"))
      (node (ref "U46") (pin "6") (pinfunction "6_6") (pintype "unspecified"))
      (node (ref "U49") (pin "3") (pinfunction "3_3") (pintype "unspecified"))
      (node (ref "U49") (pin "5") (pinfunction "5_5") (pintype "unspecified"))
      (node (ref "U49") (pin "6") (pinfunction "6_6") (pintype "unspecified"))
      (node (ref "U5") (pin "12") (pinfunction "VSSA_12") (pintype "unspecified"))
      (node (ref "U5") (pin "18") (pinfunction "VSS_18") (pintype "unspecified"))
      (node (ref "U5") (pin "63") (pinfunction "VSS_63") (pintype "unspecified"))
      (node (ref "U50") (pin "3") (pinfunction "3_3") (pintype "unspecified"))
      (node (ref "U50") (pin "5") (pinfunction "5_5") (pintype "unspecified"))
      (node (ref "U50") (pin "6") (pinfunction "6_6") (pintype "unspecified"))
      (node (ref "U52") (pin "2") (pinfunction "VSS_2") (pintype "input"))
      (node (ref "U52") (pin "4") (pinfunction "NC_4") (pintype "input"))
      (node (ref "U53") (pin "2") (pinfunction "VSS_2") (pintype "input"))
      (node (ref "U53") (pin "4") (pinfunction "NC_4") (pintype "input"))
      (node (ref "U59") (pin "3") (pinfunction "3_3") (pintype "unspecified"))
      (node (ref "U59") (pin "5") (pinfunction "5_5") (pintype "unspecified"))
      (node (ref "U59") (pin "6") (pinfunction "6_6") (pintype "unspecified"))
      (node (ref "U6") (pin "8") (pinfunction "GND_8") (pintype "input"))
      (node (ref "U60") (pin "3") (pinfunction "3_3") (pintype "unspecified"))
      (node (ref "U60") (pin "5") (pinfunction "5_5") (pintype "unspecified"))
      (node (ref "U60") (pin "6") (pinfunction "6_6") (pintype "unspecified"))
      (node (ref "U61") (pin "6") (pinfunction "6_6") (pintype "unspecified"))
      (node (ref "U61") (pin "7") (pinfunction "7_7") (pintype "unspecified"))
      (node (ref "U61") (pin "8") (pinfunction "8_8") (pintype "unspecified"))
      (node (ref "U62") (pin "6") (pinfunction "6_6") (pintype "unspecified"))
      (node (ref "U62") (pin "7") (pinfunction "7_7") (pintype "unspecified"))
      (node (ref "U62") (pin "8") (pinfunction "8_8") (pintype "unspecified"))
      (node (ref "U7") (pin "4") (pinfunction "4_4") (pintype "unspecified"))
      (node (ref "U7") (pin "7") (pinfunction "7_7") (pintype "unspecified"))
      (node (ref "U7") (pin "8") (pinfunction "8_8") (pintype "unspecified"))
      (node (ref "X3") (pin "2") (pinfunction "GND_2") (pintype "unspecified"))
      (node (ref "X3") (pin "4") (pinfunction "GND_4") (pintype "unspecified"))
    )
    (net (code "59") (name "Net-(H1-Pad1)") (class "Default")
      (node (ref "H1") (pin "1") (pinfunction "1_1") (pintype "input"))
      (node (ref "R15") (pin "2") (pinfunction "2_2") (pintype "input"))
    )
    (net (code "60") (name "Net-(H2-Pad1)") (class "Default")
      (node (ref "H2") (pin "1") (pinfunction "1_1") (pintype "input"))
      (node (ref "R17") (pin "2") (pinfunction "2_2") (pintype "input"))
    )
    (net (code "61") (name "Net-(LED1-Pad1)") (class "Default")
      (node (ref "LED1") (pin "1") (pinfunction "1_1") (pintype "unspecified"))
      (node (ref "R12") (pin "2") (pinfunction "2_2") (pintype "input"))
    )
    (net (code "62") (name "Net-(LED1-Pad2)") (class "Default")
      (node (ref "LED1") (pin "2") (pinfunction "2_2") (pintype "unspecified"))
      (node (ref "R13") (pin "2") (pinfunction "2_2") (pintype "input"))
    )
    (net (code "63") (name "Net-(LED1-Pad4)") (class "Default")
      (node (ref "LED1") (pin "4") (pinfunction "4_4") (pintype "unspecified"))
      (node (ref "R14") (pin "2") (pinfunction "2_2") (pintype "input"))
    )
    (net (code "64") (name "Net-(R3-Pad1)") (class "Default")
      (node (ref "R3") (pin "1") (pinfunction "1_1") (pintype "input"))
      (node (ref "SW3") (pin "1") (pinfunction "1_1") (pintype "unspecified"))
    )
    (net (code "65") (name "Net-(R4-Pad1)") (class "Default")
      (node (ref "R4") (pin "1") (pinfunction "1_1") (pintype "input"))
      (node (ref "SW4") (pin "1") (pinfunction "1_1") (pintype "unspecified"))
    )
    (net (code "66") (name "Net-(U2-SDO)") (class "Default")
      (node (ref "R9") (pin "2") (pinfunction "2_2") (pintype "input"))
      (node (ref "U2") (pin "5") (pinfunction "SDO_5") (pintype "unspecified"))
    )
    (net (code "67") (name "Net-(U4-C1)") (class "Default")
      (node (ref "C10") (pin "2") (pinfunction "2_2") (pintype "input"))
      (node (ref "U4") (pin "4") (pinfunction "C1_4") (pintype "unspecified"))
    )
    (net (code "68") (name "Net-(U5A-VCAP_1)") (class "Default")
      (node (ref "C21") (pin "2") (pinfunction "2_2") (pintype "input"))
      (node (ref "U5") (pin "31") (pinfunction "VCAP_1_31") (pintype "unspecified"))
    )
    (net (code "69") (name "Net-(U5A-VCAP_2)") (class "Default")
      (node (ref "C20") (pin "2") (pinfunction "2_2") (pintype "input"))
      (node (ref "U5") (pin "47") (pinfunction "VCAP_2_47") (pintype "unspecified"))
    )
    (net (code "70") (name "unconnected-(U1-INT1{slash}INT-Pad4)") (class "Default")
      (node (ref "U1") (pin "4") (pinfunction "INT1/INT_4") (pintype "unspecified+no_connect"))
    )
    (net (code "71") (name "unconnected-(U1-INT2{slash}FSYNC{slash}CLKIN-Pad9)") (class "Default")
      (node (ref "U1") (pin "9") (pinfunction "INT2/FSYNC/CLKIN_9") (pintype "unspecified+no_connect"))
    )
    (net (code "72") (name "unconnected-(U1-RESV-Pad2)") (class "Default")
      (node (ref "U1") (pin "2") (pinfunction "RESV_2") (pintype "unspecified+no_connect"))
    )
    (net (code "73") (name "unconnected-(U1-RESV-Pad3)") (class "Default")
      (node (ref "U1") (pin "3") (pinfunction "RESV_3") (pintype "unspecified+no_connect"))
    )
    (net (code "74") (name "unconnected-(U1-RESV-Pad10)") (class "Default")
      (node (ref "U1") (pin "10") (pinfunction "RESV_10") (pintype "unspecified+no_connect"))
    )
    (net (code "75") (name "unconnected-(U2-CSB-Pad2)") (class "Default")
      (node (ref "U2") (pin "2") (pinfunction "CSB_2") (pintype "unspecified+no_connect"))
    )
    (net (code "76") (name "unconnected-(U4-DRDY-Pad8)") (class "Default")
      (node (ref "U4") (pin "8") (pinfunction "DRDY_8") (pintype "unspecified+no_connect"))
    )
    (net (code "77") (name "unconnected-(U4-INT-Pad7)") (class "Default")
      (node (ref "U4") (pin "7") (pinfunction "INT_7") (pintype "unspecified+no_connect"))
    )
  )
)
